# MainBoard_MCU_RF.net
KiCad netlist of a schematic drawn in Altium Designer
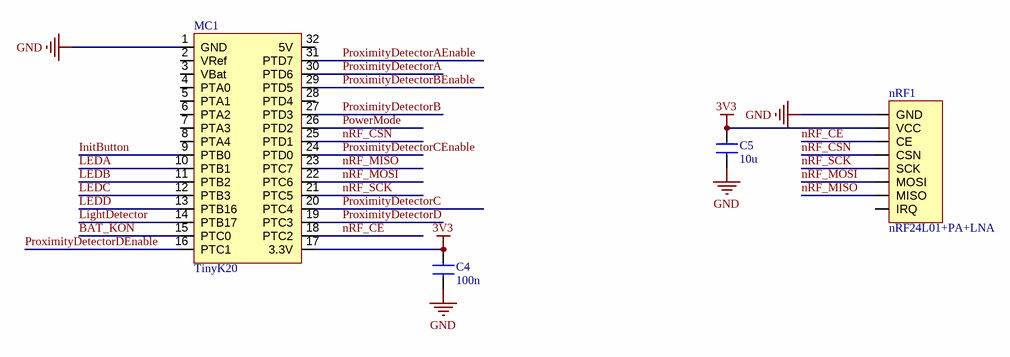
[diagram p0: MainBoard_MCU_RF.SchDoc]

(export (version "E")
  (design (tool "Eeschema 10.0.6"))
  (components
    (comp (ref "C4")
      (value "100n")
      (footprint "0805_C")
      (description "Normaler Kondensator")
      (libsource (lib "MainBoard") (part "C?"))
    )
    (comp (ref "C5")
      (value "10u")
      (footprint "0805_C")
      (description "Normaler Kondensator")
      (libsource (lib "MainBoard") (part "C?"))
    )
    (comp (ref "MC1") (value "TinyK20") (footprint "DIP32") (libsource (lib "MainBoard") (part "TinyK20")))
    (comp (ref "nRF1")
      (value "nRF24L01+PA+LNA")
      (footprint "CON_THT_2x4P_RM2.54_Stiftl")
      (libsource (lib "MainBoard") (part "Bluefruit"))
    )
  )
  (nets
    (net (code "1") (name "/BAT_KON") (class "Default")
      (node (ref "MC1") (pin "15") (pinfunction "PTC0_15") (pintype "passive"))
    )
    (net (code "2") (name "/InitButton") (class "Default")
      (node (ref "MC1") (pin "9") (pinfunction "PTB0_9") (pintype "passive"))
    )
    (net (code "3") (name "/LEDA") (class "Default")
      (node (ref "MC1") (pin "10") (pinfunction "PTB1_10") (pintype "passive"))
    )
    (net (code "4") (name "/LEDB") (class "Default")
      (node (ref "MC1") (pin "11") (pinfunction "PTB2_11") (pintype "passive"))
    )
    (net (code "5") (name "/LEDC") (class "Default")
      (node (ref "MC1") (pin "12") (pinfunction "PTB3_12") (pintype "passive"))
    )
    (net (code "6") (name "/LEDD") (class "Default")
      (node (ref "MC1") (pin "13") (pinfunction "PTB16_13") (pintype "passive"))
    )
    (net (code "7") (name "/LightDetector") (class "Default")
      (node (ref "MC1") (pin "14") (pinfunction "PTB17_14") (pintype "passive"))
    )
    (net (code "8") (name "/PowerMode") (class "Default")
      (node (ref "MC1") (pin "26") (pinfunction "PTD2_26") (pintype "passive"))
    )
    (net (code "9") (name "/ProximityDetectorA") (class "Default")
      (node (ref "MC1") (pin "30") (pinfunction "PTD6_30") (pintype "passive"))
    )
    (net (code "10") (name "/ProximityDetectorAEnable") (class "Default")
      (node (ref "MC1") (pin "31") (pinfunction "PTD7_31") (pintype "passive"))
    )
    (net (code "11") (name "/ProximityDetectorB") (class "Default")
      (node (ref "MC1") (pin "27") (pinfunction "PTD3_27") (pintype "passive"))
    )
    (net (code "12") (name "/ProximityDetectorBEnable") (class "Default")
      (node (ref "MC1") (pin "29") (pinfunction "PTD5_29") (pintype "passive"))
    )
    (net (code "13") (name "/ProximityDetectorC") (class "Default")
      (node (ref "MC1") (pin "20") (pinfunction "PTC4_20") (pintype "passive"))
    )
    (net (code "14") (name "/ProximityDetectorCEnable") (class "Default")
      (node (ref "MC1") (pin "24") (pinfunction "PTD0_24") (pintype "passive"))
    )
    (net (code "15") (name "/ProximityDetectorD") (class "Default")
      (node (ref "MC1") (pin "19") (pinfunction "PTC3_19") (pintype "passive"))
    )
    (net (code "16") (name "/ProximityDetectorDEnable") (class "Default")
      (node (ref "MC1") (pin "16") (pinfunction "PTC1_16") (pintype "passive"))
    )
    (net (code "17") (name "/nRF_CE") (class "Default")
      (node (ref "MC1") (pin "18") (pinfunction "PTC2_18") (pintype "passive"))
      (node (ref "nRF1") (pin "3") (pinfunction "CE_3") (pintype "passive"))
    )
    (net (code "18") (name "/nRF_CSN") (class "Default")
      (node (ref "MC1") (pin "25") (pinfunction "PTD1_25") (pintype "passive"))
      (node (ref "nRF1") (pin "4") (pinfunction "CSN_4") (pintype "passive"))
    )
    (net (code "19") (name "/nRF_MISO") (class "Default")
      (node (ref "MC1") (pin "23") (pinfunction "PTC7_23") (pintype "passive"))
      (node (ref "nRF1") (pin "7") (pinfunction "MISO_7") (pintype "passive"))
    )
    (net (code "20") (name "/nRF_MOSI") (class "Default")
      (node (ref "MC1") (pin "22") (pinfunction "PTC6_22") (pintype "passive"))
      (node (ref "nRF1") (pin "6") (pinfunction "MOSI_6") (pintype "passive"))
    )
    (net (code "21") (name "/nRF_SCK") (class "Default")
      (node (ref "MC1") (pin "21") (pinfunction "PTC5_21") (pintype "passive"))
      (node (ref "nRF1") (pin "5") (pinfunction "SCK_5") (pintype "passive"))
    )
    (net (code "22") (name "3V3") (class "Default")
      (node (ref "C4") (pin "2") (pinfunction "2_2") (pintype "passive"))
      (node (ref "C5") (pin "2") (pinfunction "2_2") (pintype "passive"))
      (node (ref "MC1") (pin "17") (pinfunction "3.3V_17") (pintype "passive"))
      (node (ref "nRF1") (pin "2") (pinfunction "VCC_2") (pintype "passive"))
    )
    (net (code "23") (name "GND") (class "Default")
      (node (ref "C4") (pin "1") (pinfunction "1_1") (pintype "passive"))
      (node (ref "C5") (pin "1") (pinfunction "1_1") (pintype "passive"))
      (node (ref "MC1") (pin "1") (pinfunction "GND_1") (pintype "passive"))
      (node (ref "nRF1") (pin "1") (pinfunction "GND_1") (pintype "passive"))
    )
    (net (code "24") (name "unconnected-(MC1-5V-Pad32)") (class "Default")
      (node (ref "MC1") (pin "32") (pinfunction "5V_32") (pintype "passive"))
    )
    (net (code "25") (name "unconnected-(MC1-PTA0-Pad4)") (class "Default")
      (node (ref "MC1") (pin "4") (pinfunction "PTA0_4") (pintype "passive"))
    )
    (net (code "26") (name "unconnected-(MC1-PTA1-Pad5)") (class "Default")
      (node (ref "MC1") (pin "5") (pinfunction "PTA1_5") (pintype "passive"))
    )
    (net (code "27") (name "unconnected-(MC1-PTA2-Pad6)") (class "Default")
      (node (ref "MC1") (pin "6") (pinfunction "PTA2_6") (pintype "passive"))
    )
    (net (code "28") (name "unconnected-(MC1-PTA3-Pad7)") (class "Default")
      (node (ref "MC1") (pin "7") (pinfunction "PTA3_7") (pintype "passive"))
    )
    (net (code "29") (name "unconnected-(MC1-PTA4-Pad8)") (class "Default")
      (node (ref "MC1") (pin "8") (pinfunction "PTA4_8") (pintype "passive"))
    )
    (net (code "30") (name "unconnected-(MC1-PTD4-Pad28)") (class "Default")
      (node (ref "MC1") (pin "28") (pinfunction "PTD4_28") (pintype "passive"))
    )
    (net (code "31") (name "unconnected-(MC1-VBat-Pad3)") (class "Default")
      (node (ref "MC1") (pin "3") (pinfunction "VBat_3") (pintype "passive"))
    )
    (net (code "32") (name "unconnected-(MC1-VRef-Pad2)") (class "Default")
      (node (ref "MC1") (pin "2") (pinfunction "VRef_2") (pintype "passive"))
    )
    (net (code "33") (name "unconnected-(nRF1-IRQ-Pad8)") (class "Default")
      (node (ref "nRF1") (pin "8") (pinfunction "IRQ_8") (pintype "passive"))
    )
  )
)
